# Adafruit_LIS3DH_Original.net
KiCad netlist of a schematic drawn in EAGLE
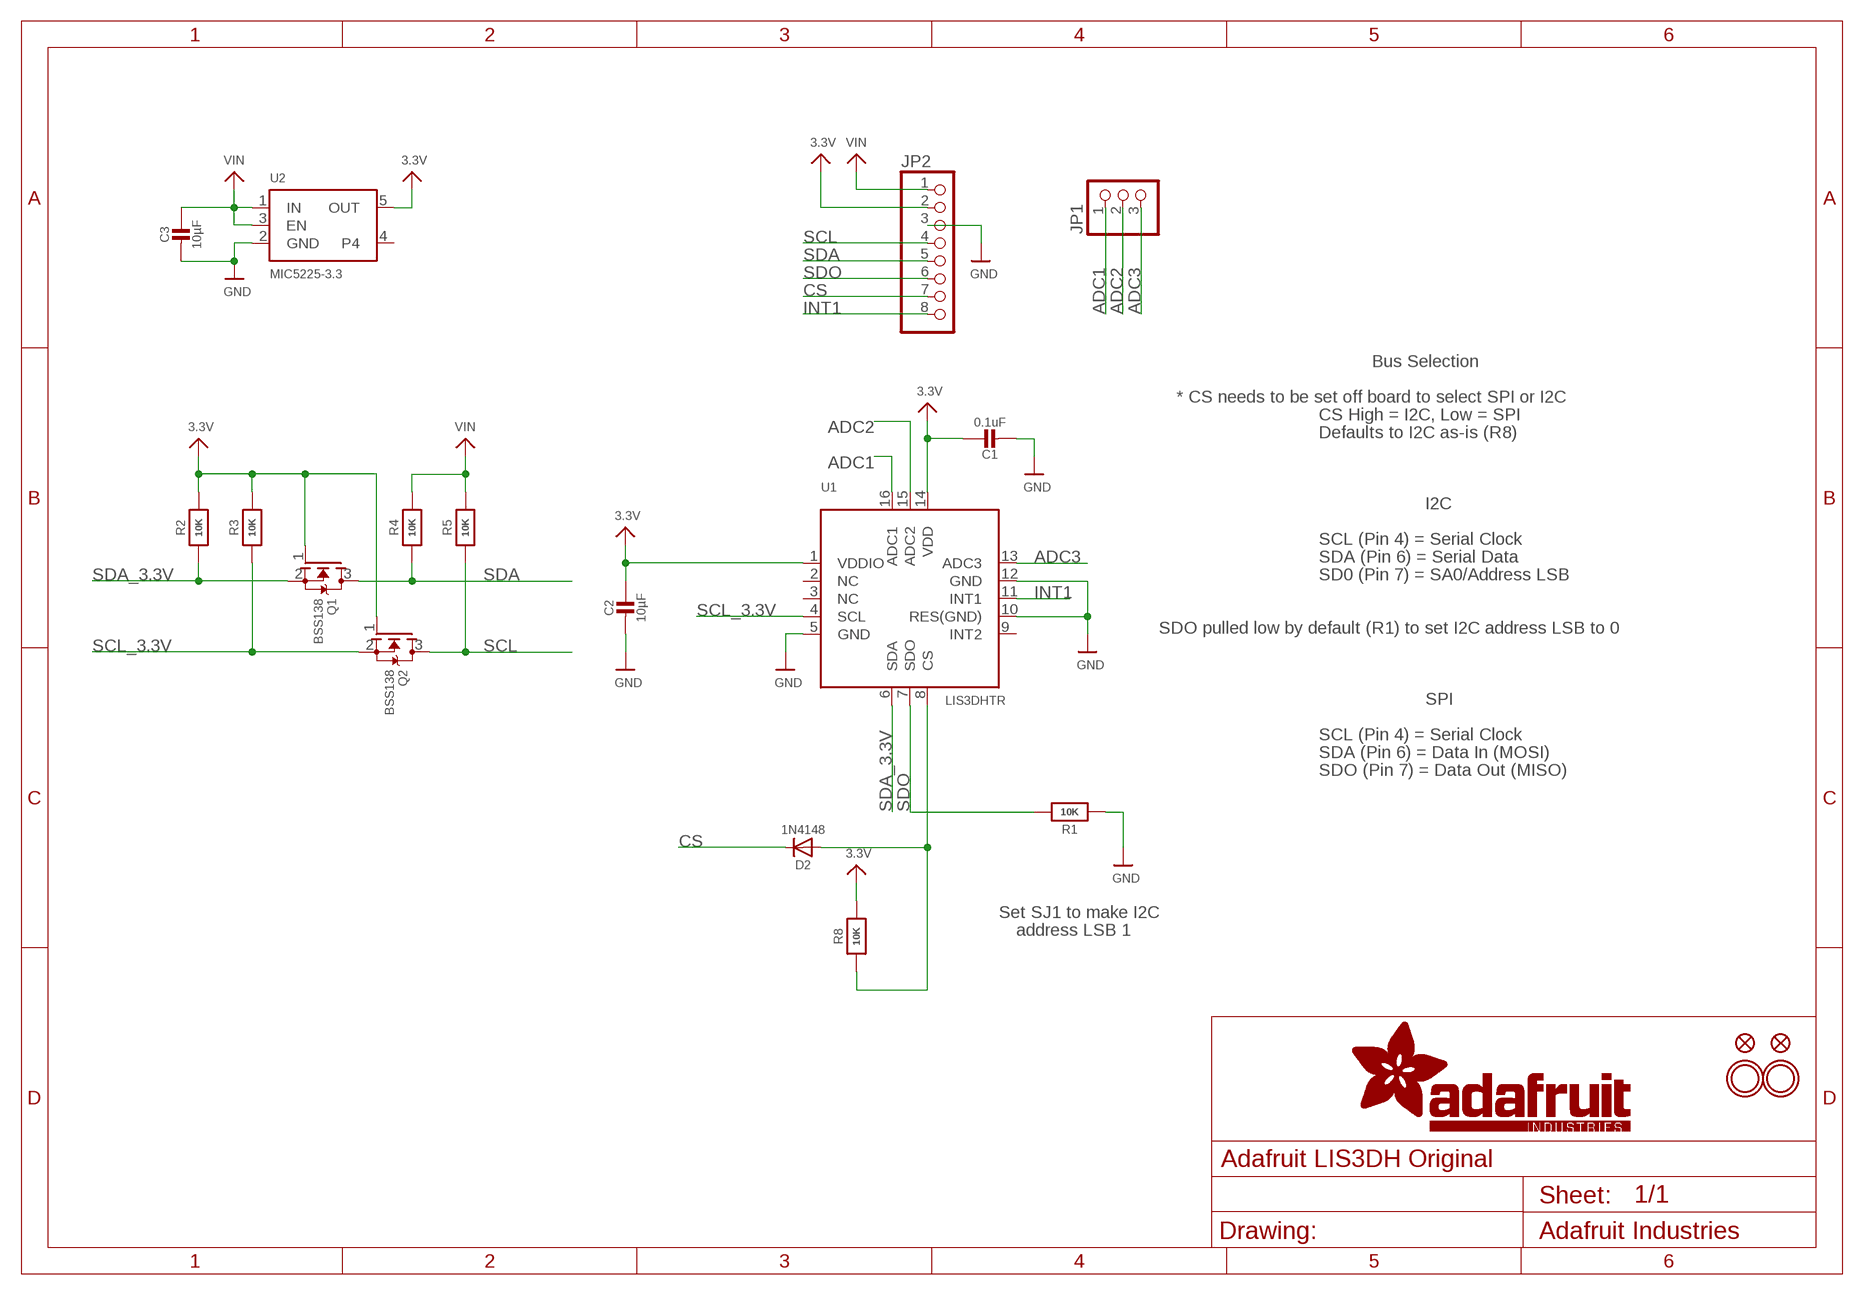
[diagram p0: schematic, sheet 1]

(export (version "E")
  (design (tool "Eeschema 10.0.6"))
  (components
    (comp (ref "C1")
      (value "0.1uF")
      (footprint "eagle-import:0805_10MGAP")
      (libsource (lib "eagle-import") (part "CAP_CERAMIC0805_10MGAP"))
    )
    (comp (ref "C2")
      (value "10µF")
      (footprint "eagle-import:0805-NO")
      (libsource (lib "eagle-import") (part "CAP_CERAMIC0805-NOOUTLINE"))
    )
    (comp (ref "C3")
      (value "10µF")
      (footprint "eagle-import:0805-NO")
      (libsource (lib "eagle-import") (part "CAP_CERAMIC0805-NOOUTLINE"))
    )
    (comp (ref "D2")
      (value "1N4148")
      (footprint "eagle-import:SOD-323")
      (libsource (lib "eagle-import") (part "DIODESOD-323"))
    )
    (comp (ref "FID1")
      (value "FIDUCIAL\"\"")
      (footprint "eagle-import:FIDUCIAL_1MM")
      (libsource (lib "eagle-import") (part "FIDUCIAL{dblquote}{dblquote}"))
    )
    (comp (ref "FID2")
      (value "FIDUCIAL\"\"")
      (footprint "eagle-import:FIDUCIAL_1MM")
      (libsource (lib "eagle-import") (part "FIDUCIAL{dblquote}{dblquote}"))
    )
    (comp (ref "JP1")
      (value "HEADER-1X3ROUND")
      (footprint "eagle-import:1X03_ROUND")
      (libsource (lib "eagle-import") (part "HEADER-1X3ROUND"))
    )
    (comp (ref "JP2")
      (value "HEADER-1X870MIL")
      (footprint "eagle-import:1X08_ROUND_70")
      (libsource (lib "eagle-import") (part "HEADER-1X870MIL"))
    )
    (comp (ref "Q1")
      (value "BSS138")
      (footprint "eagle-import:SOT23-WIDE")
      (libsource (lib "eagle-import") (part "MOSFET-NWIDE"))
    )
    (comp (ref "Q2")
      (value "BSS138")
      (footprint "eagle-import:SOT23-WIDE")
      (libsource (lib "eagle-import") (part "MOSFET-NWIDE"))
    )
    (comp (ref "R1")
      (value "10K")
      (footprint "eagle-import:0805-NO")
      (libsource (lib "eagle-import") (part "RESISTOR0805_NOOUTLINE"))
    )
    (comp (ref "R2")
      (value "10K")
      (footprint "eagle-import:0805-NO")
      (libsource (lib "eagle-import") (part "RESISTOR0805_NOOUTLINE"))
    )
    (comp (ref "R3")
      (value "10K")
      (footprint "eagle-import:0805-NO")
      (libsource (lib "eagle-import") (part "RESISTOR0805_NOOUTLINE"))
    )
    (comp (ref "R4")
      (value "10K")
      (footprint "eagle-import:0805-NO")
      (libsource (lib "eagle-import") (part "RESISTOR0805_NOOUTLINE"))
    )
    (comp (ref "R5")
      (value "10K")
      (footprint "eagle-import:0805-NO")
      (libsource (lib "eagle-import") (part "RESISTOR0805_NOOUTLINE"))
    )
    (comp (ref "R8")
      (value "10K")
      (footprint "eagle-import:0805-NO")
      (libsource (lib "eagle-import") (part "RESISTOR0805_NOOUTLINE"))
    )
    (comp (ref "U$10")
      (value "MOUNTINGHOLE2.5")
      (footprint "eagle-import:MOUNTINGHOLE_2.5_PLATED")
      (libsource (lib "eagle-import") (part "MOUNTINGHOLE2.5"))
    )
    (comp (ref "U$13")
      (value "MOUNTINGHOLE2.5")
      (footprint "eagle-import:MOUNTINGHOLE_2.5_PLATED")
      (libsource (lib "eagle-import") (part "MOUNTINGHOLE2.5"))
    )
    (comp (ref "U1")
      (value "LIS3DHTR")
      (footprint "eagle-import:LGA16_3X3MM")
      (libsource (lib "eagle-import") (part "ACCEL_LIS3DHTR"))
    )
    (comp (ref "U2")
      (value "MIC5225-3.3")
      (footprint "eagle-import:SOT23-5")
      (libsource (lib "eagle-import") (part "VREG_SOT23-5"))
    )
  )
  (nets
    (net (code "1") (name "/ADC1") (class "Default")
      (node (ref "JP1") (pin "1") (pinfunction "1_1") (pintype "passive"))
      (node (ref "U1") (pin "16") (pinfunction "ADC1_16") (pintype "input"))
    )
    (net (code "2") (name "/ADC2") (class "Default")
      (node (ref "JP1") (pin "2") (pinfunction "2_2") (pintype "passive"))
      (node (ref "U1") (pin "15") (pinfunction "ADC2_15") (pintype "input"))
    )
    (net (code "3") (name "/ADC3") (class "Default")
      (node (ref "JP1") (pin "3") (pinfunction "3_3") (pintype "passive"))
      (node (ref "U1") (pin "13") (pinfunction "ADC3_13") (pintype "input"))
    )
    (net (code "4") (name "/CS") (class "Default")
      (node (ref "D2") (pin "C") (pinfunction "C_C") (pintype "passive"))
      (node (ref "JP2") (pin "7") (pinfunction "7_7") (pintype "passive"))
    )
    (net (code "5") (name "/INT1") (class "Default")
      (node (ref "JP2") (pin "8") (pinfunction "8_8") (pintype "passive"))
      (node (ref "U1") (pin "11") (pinfunction "INT1_11") (pintype "output"))
    )
    (net (code "6") (name "/SCL") (class "Default")
      (node (ref "JP2") (pin "4") (pinfunction "4_4") (pintype "passive"))
      (node (ref "Q2") (pin "3") (pinfunction "D_3") (pintype "bidirectional"))
      (node (ref "R5") (pin "1") (pinfunction "1_1") (pintype "passive"))
    )
    (net (code "7") (name "/SCL_3.3V") (class "Default")
      (node (ref "Q2") (pin "2") (pinfunction "S_2") (pintype "bidirectional"))
      (node (ref "R3") (pin "1") (pinfunction "1_1") (pintype "passive"))
      (node (ref "U1") (pin "4") (pinfunction "SCL_4") (pintype "bidirectional"))
    )
    (net (code "8") (name "/SDA") (class "Default")
      (node (ref "JP2") (pin "5") (pinfunction "5_5") (pintype "passive"))
      (node (ref "Q1") (pin "3") (pinfunction "D_3") (pintype "bidirectional"))
      (node (ref "R4") (pin "1") (pinfunction "1_1") (pintype "passive"))
    )
    (net (code "9") (name "/SDA_3.3V") (class "Default")
      (node (ref "Q1") (pin "2") (pinfunction "S_2") (pintype "bidirectional"))
      (node (ref "R2") (pin "1") (pinfunction "1_1") (pintype "passive"))
      (node (ref "U1") (pin "6") (pinfunction "SDA_6") (pintype "bidirectional"))
    )
    (net (code "10") (name "/SDO") (class "Default")
      (node (ref "JP2") (pin "6") (pinfunction "6_6") (pintype "passive"))
      (node (ref "R1") (pin "2") (pinfunction "2_2") (pintype "passive"))
      (node (ref "U1") (pin "7") (pinfunction "SDO_7") (pintype "bidirectional"))
    )
    (net (code "11") (name "3.3V") (class "Default")
      (node (ref "C1") (pin "1") (pinfunction "1_1") (pintype "passive"))
      (node (ref "C2") (pin "1") (pinfunction "1_1") (pintype "passive"))
      (node (ref "JP2") (pin "2") (pinfunction "2_2") (pintype "passive"))
      (node (ref "Q1") (pin "1") (pinfunction "G_1") (pintype "bidirectional"))
      (node (ref "Q2") (pin "1") (pinfunction "G_1") (pintype "bidirectional"))
      (node (ref "R2") (pin "2") (pinfunction "2_2") (pintype "passive"))
      (node (ref "R3") (pin "2") (pinfunction "2_2") (pintype "passive"))
      (node (ref "R8") (pin "2") (pinfunction "2_2") (pintype "passive"))
      (node (ref "U1") (pin "1") (pinfunction "VDDIO_1") (pintype "power_in"))
      (node (ref "U1") (pin "14") (pinfunction "VDD_14") (pintype "power_in"))
      (node (ref "U2") (pin "5") (pinfunction "OUT_5") (pintype "power_in"))
    )
    (net (code "12") (name "GND") (class "Default")
      (node (ref "C1") (pin "2") (pinfunction "2_2") (pintype "passive"))
      (node (ref "C2") (pin "2") (pinfunction "2_2") (pintype "passive"))
      (node (ref "C3") (pin "2") (pinfunction "2_2") (pintype "passive"))
      (node (ref "JP2") (pin "3") (pinfunction "3_3") (pintype "passive"))
      (node (ref "R1") (pin "1") (pinfunction "1_1") (pintype "passive"))
      (node (ref "U1") (pin "10") (pinfunction "RES(GND)_10") (pintype "bidirectional"))
      (node (ref "U1") (pin "12") (pinfunction "GND_12") (pintype "power_in"))
      (node (ref "U1") (pin "5") (pinfunction "GND_5") (pintype "power_in"))
      (node (ref "U2") (pin "2") (pinfunction "GND_2") (pintype "power_in"))
    )
    (net (code "13") (name "Net-(U1-CS)") (class "Default")
      (node (ref "D2") (pin "A") (pinfunction "A_A") (pintype "passive"))
      (node (ref "R8") (pin "1") (pinfunction "1_1") (pintype "passive"))
      (node (ref "U1") (pin "8") (pinfunction "CS_8") (pintype "input"))
    )
    (net (code "14") (name "VIN") (class "Default")
      (node (ref "C3") (pin "1") (pinfunction "1_1") (pintype "passive"))
      (node (ref "JP2") (pin "1") (pinfunction "1_1") (pintype "passive"))
      (node (ref "R4") (pin "2") (pinfunction "2_2") (pintype "passive"))
      (node (ref "R5") (pin "2") (pinfunction "2_2") (pintype "passive"))
      (node (ref "U2") (pin "1") (pinfunction "IN_1") (pintype "power_in"))
      (node (ref "U2") (pin "3") (pinfunction "EN_3") (pintype "input"))
    )
    (net (code "15") (name "unconnected-(U1-INT2-Pad9)") (class "Default")
      (node (ref "U1") (pin "9") (pinfunction "INT2_9") (pintype "output"))
    )
    (net (code "16") (name "unconnected-(U1-NC-Pad2)") (class "Default")
      (node (ref "U1") (pin "2") (pinfunction "NC_2") (pintype "no_connect"))
    )
    (net (code "17") (name "unconnected-(U1-NC-Pad3)") (class "Default")
      (node (ref "U1") (pin "3") (pinfunction "NC_3") (pintype "no_connect"))
    )
    (net (code "18") (name "unconnected-(U2-P4-Pad4)") (class "Default")
      (node (ref "U2") (pin "4") (pinfunction "P4_4") (pintype "bidirectional"))
    )
  )
)
